# 2016_CARTE_MOFSET.net
KiCad netlist of a schematic drawn in Altium Designer
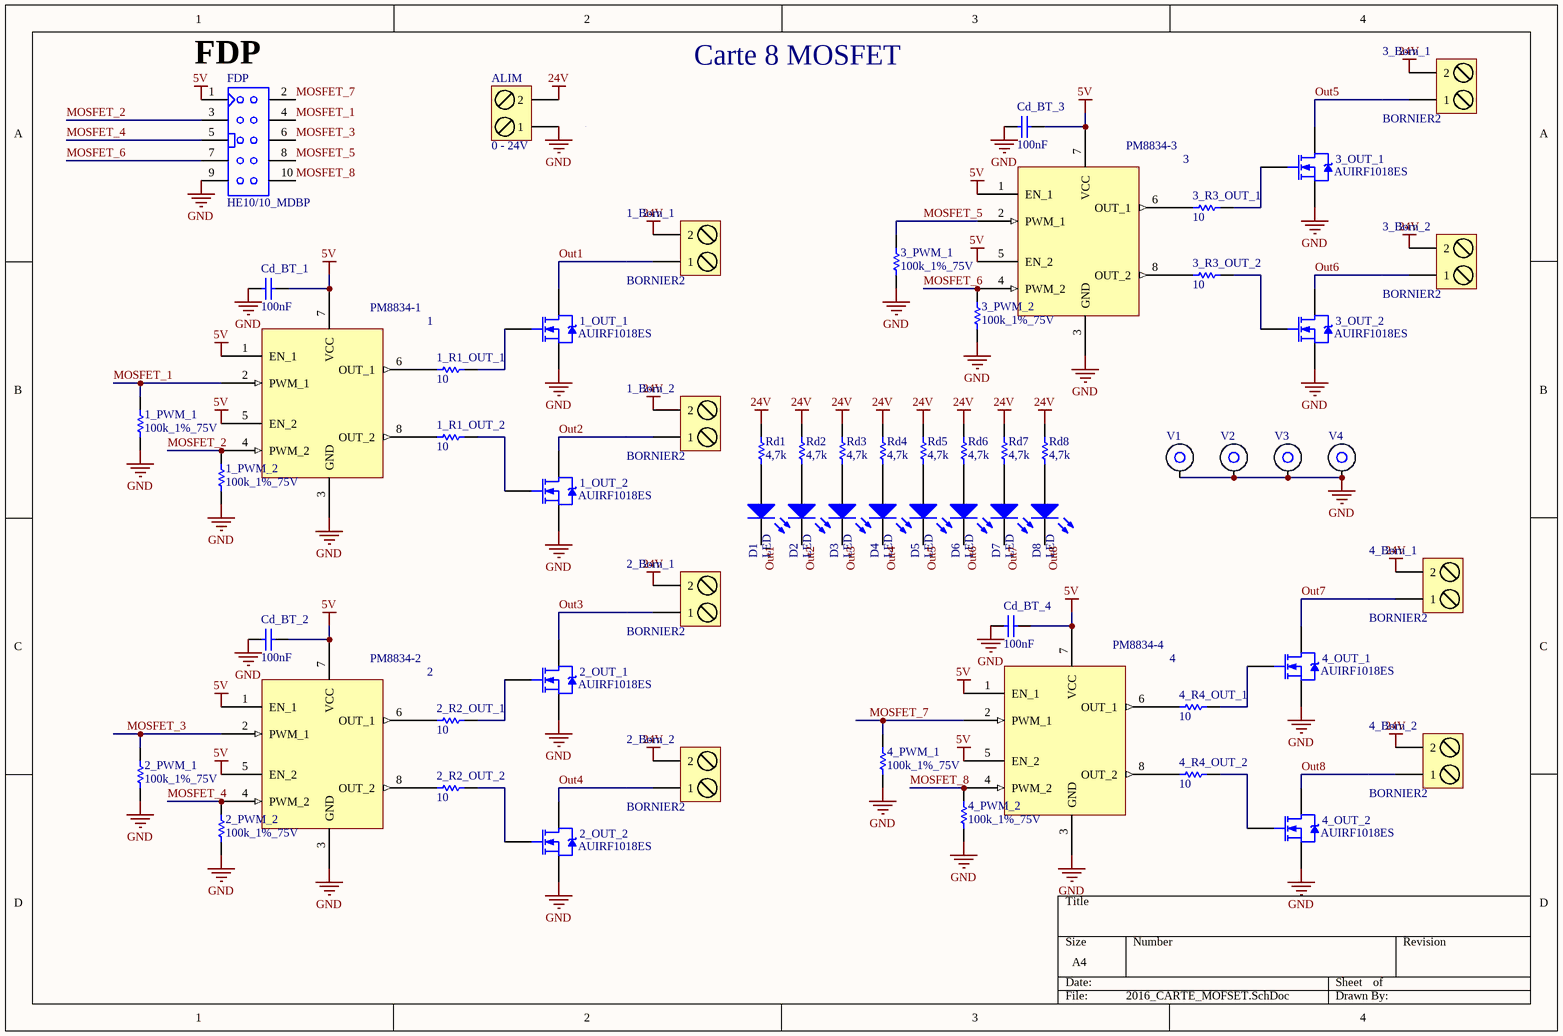
[diagram p0: 2016_CARTE_MOFSET.SchDoc]

(export (version "E")
  (design (tool "Eeschema 10.0.6"))
  (components
    (comp (ref "1")
      (value "PM8834-1")
      (footprint "SO8_N")
      (description "4 A dual low-side MOSFET driver")
      (libsource (lib "_ROBOT") (part "PM8834"))
    )
    (comp (ref "1_Born_1")
      (value "BORNIER2")
      (footprint "BORNIER2")
      (description "Terminal blocks, 2 pins, pitch=5mm")
      (libsource (lib "Connecteur") (part "BORNIER2"))
    )
    (comp (ref "1_Born_2")
      (value "BORNIER2")
      (footprint "BORNIER2")
      (description "Terminal blocks, 2 pins, pitch=5mm")
      (libsource (lib "Connecteur") (part "BORNIER2"))
    )
    (comp (ref "1_OUT_1")
      (value "AUIRF1018ES")
      (footprint "D2PAK_GROS_PAD")
      (description "HEXFET N-Channel Power MOSFET")
      (fields (field (name "PUBLISHER") "Altium Limited"))
      (libsource (lib "IR Discrete MOSFET - Power") (part "IRF1010S"))
    )
    (comp (ref "1_OUT_2")
      (value "AUIRF1018ES")
      (footprint "D2PAK_GROS_PAD")
      (description "HEXFET N-Channel Power MOSFET")
      (fields (field (name "PUBLISHER") "Altium Limited"))
      (libsource (lib "IR Discrete MOSFET - Power") (part "IRF1010S"))
    )
    (comp (ref "1_PWM_1")
      (value "100k_1%_75V")
      (footprint "R1206_N")
      (description "Resistor")
      (fields (field (name "PUBLISHER") "Altium Limited"))
      (libsource (lib "DG_Resistance") (part "Resistor"))
    )
    (comp (ref "1_PWM_2")
      (value "100k_1%_75V")
      (footprint "R1206_N")
      (description "Resistor")
      (fields (field (name "PUBLISHER") "Altium Limited"))
      (libsource (lib "DG_Resistance") (part "Resistor"))
    )
    (comp (ref "1_R1_OUT_1")
      (value "10")
      (footprint "R1206_N")
      (description "Resistor")
      (fields (field (name "PUBLISHER") "Altium Limited"))
      (libsource (lib "_ROBOT") (part "Resistor"))
    )
    (comp (ref "1_R1_OUT_2")
      (value "10")
      (footprint "R1206_N")
      (description "Resistor")
      (fields (field (name "PUBLISHER") "Altium Limited"))
      (libsource (lib "_ROBOT") (part "Resistor"))
    )
    (comp (ref "2")
      (value "PM8834-2")
      (footprint "SO8_N")
      (description "4 A dual low-side MOSFET driver")
      (libsource (lib "_ROBOT") (part "PM8834"))
    )
    (comp (ref "2_Born_1")
      (value "BORNIER2")
      (footprint "BORNIER2")
      (description "Terminal blocks, 2 pins, pitch=5mm")
      (libsource (lib "Connecteur") (part "BORNIER2"))
    )
    (comp (ref "2_Born_2")
      (value "BORNIER2")
      (footprint "BORNIER2")
      (description "Terminal blocks, 2 pins, pitch=5mm")
      (libsource (lib "Connecteur") (part "BORNIER2"))
    )
    (comp (ref "2_OUT_1")
      (value "AUIRF1018ES")
      (footprint "D2PAK_GROS_PAD")
      (description "HEXFET N-Channel Power MOSFET")
      (fields (field (name "PUBLISHER") "Altium Limited"))
      (libsource (lib "IR Discrete MOSFET - Power") (part "IRF1010S"))
    )
    (comp (ref "2_OUT_2")
      (value "AUIRF1018ES")
      (footprint "D2PAK_GROS_PAD")
      (description "HEXFET N-Channel Power MOSFET")
      (fields (field (name "PUBLISHER") "Altium Limited"))
      (libsource (lib "IR Discrete MOSFET - Power") (part "IRF1010S"))
    )
    (comp (ref "2_PWM_1")
      (value "100k_1%_75V")
      (footprint "R1206_N")
      (description "Resistor")
      (fields (field (name "PUBLISHER") "Altium Limited"))
      (libsource (lib "DG_Resistance") (part "Resistor"))
    )
    (comp (ref "2_PWM_2")
      (value "100k_1%_75V")
      (footprint "R1206_N")
      (description "Resistor")
      (fields (field (name "PUBLISHER") "Altium Limited"))
      (libsource (lib "DG_Resistance") (part "Resistor"))
    )
    (comp (ref "2_R2_OUT_1")
      (value "10")
      (footprint "R1206_N")
      (description "Resistor")
      (fields (field (name "PUBLISHER") "Altium Limited"))
      (libsource (lib "_ROBOT") (part "Resistor"))
    )
    (comp (ref "2_R2_OUT_2")
      (value "10")
      (footprint "R1206_N")
      (description "Resistor")
      (fields (field (name "PUBLISHER") "Altium Limited"))
      (libsource (lib "_ROBOT") (part "Resistor"))
    )
    (comp (ref "3")
      (value "PM8834-3")
      (footprint "SO8_N")
      (description "4 A dual low-side MOSFET driver")
      (libsource (lib "_ROBOT") (part "PM8834"))
    )
    (comp (ref "3_Born_1")
      (value "BORNIER2")
      (footprint "BORNIER2")
      (description "Terminal blocks, 2 pins, pitch=5mm")
      (libsource (lib "Connecteur") (part "BORNIER2"))
    )
    (comp (ref "3_Born_2")
      (value "BORNIER2")
      (footprint "BORNIER2")
      (description "Terminal blocks, 2 pins, pitch=5mm")
      (libsource (lib "Connecteur") (part "BORNIER2"))
    )
    (comp (ref "3_OUT_1")
      (value "AUIRF1018ES")
      (footprint "D2PAK_GROS_PAD")
      (description "HEXFET N-Channel Power MOSFET")
      (fields (field (name "PUBLISHER") "Altium Limited"))
      (libsource (lib "IR Discrete MOSFET - Power") (part "IRF1010S"))
    )
    (comp (ref "3_OUT_2")
      (value "AUIRF1018ES")
      (footprint "D2PAK_GROS_PAD")
      (description "HEXFET N-Channel Power MOSFET")
      (fields (field (name "PUBLISHER") "Altium Limited"))
      (libsource (lib "IR Discrete MOSFET - Power") (part "IRF1010S"))
    )
    (comp (ref "3_PWM_1")
      (value "100k_1%_75V")
      (footprint "R1206_N")
      (description "Resistor")
      (fields (field (name "PUBLISHER") "Altium Limited"))
      (libsource (lib "DG_Resistance") (part "Resistor"))
    )
    (comp (ref "3_PWM_2")
      (value "100k_1%_75V")
      (footprint "R1206_N")
      (description "Resistor")
      (fields (field (name "PUBLISHER") "Altium Limited"))
      (libsource (lib "DG_Resistance") (part "Resistor"))
    )
    (comp (ref "3_R3_OUT_1")
      (value "10")
      (footprint "R1206_N")
      (description "Resistor")
      (fields (field (name "PUBLISHER") "Altium Limited"))
      (libsource (lib "_ROBOT") (part "Resistor"))
    )
    (comp (ref "3_R3_OUT_2")
      (value "10")
      (footprint "R1206_N")
      (description "Resistor")
      (fields (field (name "PUBLISHER") "Altium Limited"))
      (libsource (lib "_ROBOT") (part "Resistor"))
    )
    (comp (ref "4")
      (value "PM8834-4")
      (footprint "SO8_N")
      (description "4 A dual low-side MOSFET driver")
      (libsource (lib "_ROBOT") (part "PM8834"))
    )
    (comp (ref "4_Born_1")
      (value "BORNIER2")
      (footprint "BORNIER2")
      (description "Terminal blocks, 2 pins, pitch=5mm")
      (libsource (lib "Connecteur") (part "BORNIER2"))
    )
    (comp (ref "4_Born_2")
      (value "BORNIER2")
      (footprint "BORNIER2")
      (description "Terminal blocks, 2 pins, pitch=5mm")
      (libsource (lib "Connecteur") (part "BORNIER2"))
    )
    (comp (ref "4_OUT_1")
      (value "AUIRF1018ES")
      (footprint "D2PAK_GROS_PAD")
      (description "HEXFET N-Channel Power MOSFET")
      (fields (field (name "PUBLISHER") "Altium Limited"))
      (libsource (lib "IR Discrete MOSFET - Power") (part "IRF1010S"))
    )
    (comp (ref "4_OUT_2")
      (value "AUIRF1018ES")
      (footprint "D2PAK_GROS_PAD")
      (description "HEXFET N-Channel Power MOSFET")
      (fields (field (name "PUBLISHER") "Altium Limited"))
      (libsource (lib "IR Discrete MOSFET - Power") (part "IRF1010S"))
    )
    (comp (ref "4_PWM_1")
      (value "100k_1%_75V")
      (footprint "R1206_N")
      (description "Resistor")
      (fields (field (name "PUBLISHER") "Altium Limited"))
      (libsource (lib "DG_Resistance") (part "Resistor"))
    )
    (comp (ref "4_PWM_2")
      (value "100k_1%_75V")
      (footprint "R1206_N")
      (description "Resistor")
      (fields (field (name "PUBLISHER") "Altium Limited"))
      (libsource (lib "DG_Resistance") (part "Resistor"))
    )
    (comp (ref "4_R4_OUT_1")
      (value "10")
      (footprint "R1206_N")
      (description "Resistor")
      (fields (field (name "PUBLISHER") "Altium Limited"))
      (libsource (lib "_ROBOT") (part "Resistor"))
    )
    (comp (ref "4_R4_OUT_2")
      (value "10")
      (footprint "R1206_N")
      (description "Resistor")
      (fields (field (name "PUBLISHER") "Altium Limited"))
      (libsource (lib "_ROBOT") (part "Resistor"))
    )
    (comp (ref "ALIM")
      (value "0 - 24V")
      (footprint "BORNIER2_FEM_COUDE")
      (description "Terminal blocks, 2 pins, pitch=5mm")
      (libsource (lib "miniprojet") (part "BORNIER2"))
    )
    (comp (ref "Cd_BT_1")
      (value "100nF")
      (footprint "C0805_N")
      (description "Capacitor")
      (fields (field (name "PUBLISHER") "Altium Limited"))
      (libsource (lib "_ROBOT") (part "Condensateur"))
    )
    (comp (ref "Cd_BT_2")
      (value "100nF")
      (footprint "C0805_N")
      (description "Capacitor")
      (fields (field (name "PUBLISHER") "Altium Limited"))
      (libsource (lib "_ROBOT") (part "Condensateur"))
    )
    (comp (ref "Cd_BT_3")
      (value "100nF")
      (footprint "C0805_N")
      (description "Capacitor")
      (fields (field (name "PUBLISHER") "Altium Limited"))
      (libsource (lib "_ROBOT") (part "Condensateur"))
    )
    (comp (ref "Cd_BT_4")
      (value "100nF")
      (footprint "C0805_N")
      (description "Capacitor")
      (fields (field (name "PUBLISHER") "Altium Limited"))
      (libsource (lib "_ROBOT") (part "Condensateur"))
    )
    (comp (ref "D1")
      (value "LED")
      (footprint "LED_0805")
      (description "Typical LED")
      (fields (field (name "PUBLISHER") "Altium Limited"))
      (libsource (lib "_ROBOT") (part "LED"))
    )
    (comp (ref "D2")
      (value "LED")
      (footprint "LED_0805")
      (description "Typical LED")
      (fields (field (name "PUBLISHER") "Altium Limited"))
      (libsource (lib "_ROBOT") (part "LED"))
    )
    (comp (ref "D3")
      (value "LED")
      (footprint "LED_0805")
      (description "Typical LED")
      (fields (field (name "PUBLISHER") "Altium Limited"))
      (libsource (lib "_ROBOT") (part "LED"))
    )
    (comp (ref "D4")
      (value "LED")
      (footprint "LED_0805")
      (description "Typical LED")
      (fields (field (name "PUBLISHER") "Altium Limited"))
      (libsource (lib "_ROBOT") (part "LED"))
    )
    (comp (ref "D5")
      (value "LED")
      (footprint "LED_0805")
      (description "Typical LED")
      (fields (field (name "PUBLISHER") "Altium Limited"))
      (libsource (lib "_ROBOT") (part "LED"))
    )
    (comp (ref "D6")
      (value "LED")
      (footprint "LED_0805")
      (description "Typical LED")
      (fields (field (name "PUBLISHER") "Altium Limited"))
      (libsource (lib "_ROBOT") (part "LED"))
    )
    (comp (ref "D7")
      (value "LED")
      (footprint "LED_0805")
      (description "Typical LED")
      (fields (field (name "PUBLISHER") "Altium Limited"))
      (libsource (lib "_ROBOT") (part "LED"))
    )
    (comp (ref "D8")
      (value "LED")
      (footprint "LED_0805")
      (description "Typical LED")
      (fields (field (name "PUBLISHER") "Altium Limited"))
      (libsource (lib "_ROBOT") (part "LED"))
    )
    (comp (ref "FDP")
      (value "HE10/10_MALE_DROIT_BAS_PROFIL")
      (footprint "HE10/10_M_D_BP")
      (description "EMBASE HE10/10 MALE DROIT BAS PROFIL")
      (fields (field (name "TYPE") "HE10/10_MDBP"))
      (libsource (lib "connecteurs") (part "HE10/10_MALE_DROIT_BAS_PROFIL"))
    )
    (comp (ref "Rd1")
      (value "4,7k")
      (footprint "R1206_N")
      (description "Resistor")
      (fields (field (name "PUBLISHER") "Altium Limited"))
      (libsource (lib "_ROBOT") (part "Resistor"))
    )
    (comp (ref "Rd2")
      (value "4,7k")
      (footprint "R1206_N")
      (description "Resistor")
      (fields (field (name "PUBLISHER") "Altium Limited"))
      (libsource (lib "_ROBOT") (part "Resistor"))
    )
    (comp (ref "Rd3")
      (value "4,7k")
      (footprint "R1206_N")
      (description "Resistor")
      (fields (field (name "PUBLISHER") "Altium Limited"))
      (libsource (lib "_ROBOT") (part "Resistor"))
    )
    (comp (ref "Rd4")
      (value "4,7k")
      (footprint "R1206_N")
      (description "Resistor")
      (fields (field (name "PUBLISHER") "Altium Limited"))
      (libsource (lib "_ROBOT") (part "Resistor"))
    )
    (comp (ref "Rd5")
      (value "4,7k")
      (footprint "R1206_N")
      (description "Resistor")
      (fields (field (name "PUBLISHER") "Altium Limited"))
      (libsource (lib "_ROBOT") (part "Resistor"))
    )
    (comp (ref "Rd6")
      (value "4,7k")
      (footprint "R1206_N")
      (description "Resistor")
      (fields (field (name "PUBLISHER") "Altium Limited"))
      (libsource (lib "_ROBOT") (part "Resistor"))
    )
    (comp (ref "Rd7")
      (value "4,7k")
      (footprint "R1206_N")
      (description "Resistor")
      (fields (field (name "PUBLISHER") "Altium Limited"))
      (libsource (lib "_ROBOT") (part "Resistor"))
    )
    (comp (ref "Rd8")
      (value "4,7k")
      (footprint "R1206_N")
      (description "Resistor")
      (fields (field (name "PUBLISHER") "Altium Limited"))
      (libsource (lib "_ROBOT") (part "Resistor"))
    )
    (comp (ref "V1")
      (value "Entretoise WURTH CMS")
      (footprint "ENTRETOISE_CMS")
      (description "Entretoise Wurth")
      (fields (field (name "PUBLISHER") "Damien Guitton"))
      (libsource (lib "_ROBOT") (part "Entretoise WURTH CMS"))
    )
    (comp (ref "V2")
      (value "Entretoise WURTH CMS")
      (footprint "ENTRETOISE_CMS")
      (description "Entretoise Wurth")
      (fields (field (name "PUBLISHER") "Damien Guitton"))
      (libsource (lib "_ROBOT") (part "Entretoise WURTH CMS"))
    )
    (comp (ref "V3")
      (value "Entretoise WURTH CMS")
      (footprint "ENTRETOISE_CMS")
      (description "Entretoise Wurth")
      (fields (field (name "PUBLISHER") "Damien Guitton"))
      (libsource (lib "_ROBOT") (part "Entretoise WURTH CMS"))
    )
    (comp (ref "V4")
      (value "Entretoise WURTH CMS")
      (footprint "ENTRETOISE_CMS")
      (description "Entretoise Wurth")
      (fields (field (name "PUBLISHER") "Damien Guitton"))
      (libsource (lib "_ROBOT") (part "Entretoise WURTH CMS"))
    )
  )
  (nets
    (net (code "1") (name "/MOSFET_1") (class "Default")
      (node (ref "1") (pin "2") (pinfunction "PWM_1_2") (pintype "input"))
      (node (ref "1_PWM_1") (pin "2") (pinfunction "2_2") (pintype "passive"))
      (node (ref "FDP") (pin "4") (pinfunction "4_4") (pintype "passive"))
    )
    (net (code "2") (name "/MOSFET_2") (class "Default")
      (node (ref "1") (pin "4") (pinfunction "PWM_2_4") (pintype "input"))
      (node (ref "1_PWM_2") (pin "2") (pinfunction "2_2") (pintype "passive"))
      (node (ref "FDP") (pin "3") (pinfunction "3_3") (pintype "passive"))
    )
    (net (code "3") (name "/MOSFET_3") (class "Default")
      (node (ref "2") (pin "2") (pinfunction "PWM_1_2") (pintype "input"))
      (node (ref "2_PWM_1") (pin "2") (pinfunction "2_2") (pintype "passive"))
      (node (ref "FDP") (pin "6") (pinfunction "6_6") (pintype "passive"))
    )
    (net (code "4") (name "/MOSFET_4") (class "Default")
      (node (ref "2") (pin "4") (pinfunction "PWM_2_4") (pintype "input"))
      (node (ref "2_PWM_2") (pin "2") (pinfunction "2_2") (pintype "passive"))
      (node (ref "FDP") (pin "5") (pinfunction "5_5") (pintype "passive"))
    )
    (net (code "5") (name "/MOSFET_5") (class "Default")
      (node (ref "3") (pin "2") (pinfunction "PWM_1_2") (pintype "input"))
      (node (ref "3_PWM_1") (pin "2") (pinfunction "2_2") (pintype "passive"))
      (node (ref "FDP") (pin "8") (pinfunction "8_8") (pintype "passive"))
    )
    (net (code "6") (name "/MOSFET_6") (class "Default")
      (node (ref "3") (pin "4") (pinfunction "PWM_2_4") (pintype "input"))
      (node (ref "3_PWM_2") (pin "2") (pinfunction "2_2") (pintype "passive"))
      (node (ref "FDP") (pin "7") (pinfunction "7_7") (pintype "passive"))
    )
    (net (code "7") (name "/MOSFET_7") (class "Default")
      (node (ref "4") (pin "2") (pinfunction "PWM_1_2") (pintype "input"))
      (node (ref "4_PWM_1") (pin "2") (pinfunction "2_2") (pintype "passive"))
      (node (ref "FDP") (pin "2") (pinfunction "2_2") (pintype "passive"))
    )
    (net (code "8") (name "/MOSFET_8") (class "Default")
      (node (ref "4") (pin "4") (pinfunction "PWM_2_4") (pintype "input"))
      (node (ref "4_PWM_2") (pin "2") (pinfunction "2_2") (pintype "passive"))
      (node (ref "FDP") (pin "10") (pinfunction "10_10") (pintype "passive"))
    )
    (net (code "9") (name "/Out1") (class "Default")
      (node (ref "1_Born_1") (pin "1") (pinfunction "1_1") (pintype "passive"))
      (node (ref "1_OUT_1") (pin "2") (pinfunction "D_2") (pintype "passive"))
      (node (ref "D1") (pin "2") (pinfunction "K_2") (pintype "passive"))
    )
    (net (code "10") (name "/Out2") (class "Default")
      (node (ref "1_Born_2") (pin "1") (pinfunction "1_1") (pintype "passive"))
      (node (ref "1_OUT_2") (pin "2") (pinfunction "D_2") (pintype "passive"))
      (node (ref "D2") (pin "2") (pinfunction "K_2") (pintype "passive"))
    )
    (net (code "11") (name "/Out3") (class "Default")
      (node (ref "2_Born_1") (pin "1") (pinfunction "1_1") (pintype "passive"))
      (node (ref "2_OUT_1") (pin "2") (pinfunction "D_2") (pintype "passive"))
      (node (ref "D3") (pin "2") (pinfunction "K_2") (pintype "passive"))
    )
    (net (code "12") (name "/Out4") (class "Default")
      (node (ref "2_Born_2") (pin "1") (pinfunction "1_1") (pintype "passive"))
      (node (ref "2_OUT_2") (pin "2") (pinfunction "D_2") (pintype "passive"))
      (node (ref "D4") (pin "2") (pinfunction "K_2") (pintype "passive"))
    )
    (net (code "13") (name "/Out5") (class "Default")
      (node (ref "3_Born_1") (pin "1") (pinfunction "1_1") (pintype "passive"))
      (node (ref "3_OUT_1") (pin "2") (pinfunction "D_2") (pintype "passive"))
      (node (ref "D5") (pin "2") (pinfunction "K_2") (pintype "passive"))
    )
    (net (code "14") (name "/Out6") (class "Default")
      (node (ref "3_Born_2") (pin "1") (pinfunction "1_1") (pintype "passive"))
      (node (ref "3_OUT_2") (pin "2") (pinfunction "D_2") (pintype "passive"))
      (node (ref "D6") (pin "2") (pinfunction "K_2") (pintype "passive"))
    )
    (net (code "15") (name "/Out7") (class "Default")
      (node (ref "4_Born_1") (pin "1") (pinfunction "1_1") (pintype "passive"))
      (node (ref "4_OUT_1") (pin "2") (pinfunction "D_2") (pintype "passive"))
      (node (ref "D7") (pin "2") (pinfunction "K_2") (pintype "passive"))
    )
    (net (code "16") (name "/Out8") (class "Default")
      (node (ref "4_Born_2") (pin "1") (pinfunction "1_1") (pintype "passive"))
      (node (ref "4_OUT_2") (pin "2") (pinfunction "D_2") (pintype "passive"))
      (node (ref "D8") (pin "2") (pinfunction "K_2") (pintype "passive"))
    )
    (net (code "17") (name "5V") (class "Default")
      (node (ref "1") (pin "1") (pinfunction "EN_1_1") (pintype "passive"))
      (node (ref "1") (pin "5") (pinfunction "EN_2_5") (pintype "passive"))
      (node (ref "1") (pin "7") (pinfunction "VCC_7") (pintype "power_in"))
      (node (ref "2") (pin "1") (pinfunction "EN_1_1") (pintype "passive"))
      (node (ref "2") (pin "5") (pinfunction "EN_2_5") (pintype "passive"))
      (node (ref "2") (pin "7") (pinfunction "VCC_7") (pintype "power_in"))
      (node (ref "3") (pin "1") (pinfunction "EN_1_1") (pintype "passive"))
      (node (ref "3") (pin "5") (pinfunction "EN_2_5") (pintype "passive"))
      (node (ref "3") (pin "7") (pinfunction "VCC_7") (pintype "power_in"))
      (node (ref "4") (pin "1") (pinfunction "EN_1_1") (pintype "passive"))
      (node (ref "4") (pin "5") (pinfunction "EN_2_5") (pintype "passive"))
      (node (ref "4") (pin "7") (pinfunction "VCC_7") (pintype "power_in"))
      (node (ref "Cd_BT_1") (pin "2") (pinfunction "2_2") (pintype "passive"))
      (node (ref "Cd_BT_2") (pin "2") (pinfunction "2_2") (pintype "passive"))
      (node (ref "Cd_BT_3") (pin "2") (pinfunction "2_2") (pintype "passive"))
      (node (ref "Cd_BT_4") (pin "2") (pinfunction "2_2") (pintype "passive"))
      (node (ref "FDP") (pin "1") (pinfunction "1_1") (pintype "passive"))
    )
    (net (code "18") (name "24V") (class "Default")
      (node (ref "1_Born_1") (pin "2") (pinfunction "2_2") (pintype "passive"))
      (node (ref "1_Born_2") (pin "2") (pinfunction "2_2") (pintype "passive"))
      (node (ref "2_Born_1") (pin "2") (pinfunction "2_2") (pintype "passive"))
      (node (ref "2_Born_2") (pin "2") (pinfunction "2_2") (pintype "passive"))
      (node (ref "3_Born_1") (pin "2") (pinfunction "2_2") (pintype "passive"))
      (node (ref "3_Born_2") (pin "2") (pinfunction "2_2") (pintype "passive"))
      (node (ref "4_Born_1") (pin "2") (pinfunction "2_2") (pintype "passive"))
      (node (ref "4_Born_2") (pin "2") (pinfunction "2_2") (pintype "passive"))
      (node (ref "ALIM") (pin "2") (pinfunction "2_2") (pintype "passive"))
      (node (ref "Rd1") (pin "1") (pinfunction "1_1") (pintype "passive"))
      (node (ref "Rd2") (pin "1") (pinfunction "1_1") (pintype "passive"))
      (node (ref "Rd3") (pin "1") (pinfunction "1_1") (pintype "passive"))
      (node (ref "Rd4") (pin "1") (pinfunction "1_1") (pintype "passive"))
      (node (ref "Rd5") (pin "1") (pinfunction "1_1") (pintype "passive"))
      (node (ref "Rd6") (pin "1") (pinfunction "1_1") (pintype "passive"))
      (node (ref "Rd7") (pin "1") (pinfunction "1_1") (pintype "passive"))
      (node (ref "Rd8") (pin "1") (pinfunction "1_1") (pintype "passive"))
    )
    (net (code "19") (name "GND") (class "Default")
      (node (ref "1") (pin "3") (pinfunction "GND_3") (pintype "power_in"))
      (node (ref "1_OUT_1") (pin "3") (pinfunction "S_3") (pintype "passive"))
      (node (ref "1_OUT_2") (pin "3") (pinfunction "S_3") (pintype "passive"))
      (node (ref "1_PWM_1") (pin "1") (pinfunction "1_1") (pintype "passive"))
      (node (ref "1_PWM_2") (pin "1") (pinfunction "1_1") (pintype "passive"))
      (node (ref "2") (pin "3") (pinfunction "GND_3") (pintype "power_in"))
      (node (ref "2_OUT_1") (pin "3") (pinfunction "S_3") (pintype "passive"))
      (node (ref "2_OUT_2") (pin "3") (pinfunction "S_3") (pintype "passive"))
      (node (ref "2_PWM_1") (pin "1") (pinfunction "1_1") (pintype "passive"))
      (node (ref "2_PWM_2") (pin "1") (pinfunction "1_1") (pintype "passive"))
      (node (ref "3") (pin "3") (pinfunction "GND_3") (pintype "power_in"))
      (node (ref "3_OUT_1") (pin "3") (pinfunction "S_3") (pintype "passive"))
      (node (ref "3_OUT_2") (pin "3") (pinfunction "S_3") (pintype "passive"))
      (node (ref "3_PWM_1") (pin "1") (pinfunction "1_1") (pintype "passive"))
      (node (ref "3_PWM_2") (pin "1") (pinfunction "1_1") (pintype "passive"))
      (node (ref "4") (pin "3") (pinfunction "GND_3") (pintype "power_in"))
      (node (ref "4_OUT_1") (pin "3") (pinfunction "S_3") (pintype "passive"))
      (node (ref "4_OUT_2") (pin "3") (pinfunction "S_3") (pintype "passive"))
      (node (ref "4_PWM_1") (pin "1") (pinfunction "1_1") (pintype "passive"))
      (node (ref "4_PWM_2") (pin "1") (pinfunction "1_1") (pintype "passive"))
      (node (ref "ALIM") (pin "1") (pinfunction "1_1") (pintype "passive"))
      (node (ref "Cd_BT_1") (pin "1") (pinfunction "1_1") (pintype "passive"))
      (node (ref "Cd_BT_2") (pin "1") (pinfunction "1_1") (pintype "passive"))
      (node (ref "Cd_BT_3") (pin "1") (pinfunction "1_1") (pintype "passive"))
      (node (ref "Cd_BT_4") (pin "1") (pinfunction "1_1") (pintype "passive"))
      (node (ref "FDP") (pin "9") (pinfunction "9_9") (pintype "passive"))
      (node (ref "V1") (pin "1") (pinfunction "1_1") (pintype "passive"))
      (node (ref "V2") (pin "1") (pinfunction "1_1") (pintype "passive"))
      (node (ref "V3") (pin "1") (pinfunction "1_1") (pintype "passive"))
      (node (ref "V4") (pin "1") (pinfunction "1_1") (pintype "passive"))
    )
    (net (code "20") (name "Net-(1-OUT_1)") (class "Default")
      (node (ref "1") (pin "6") (pinfunction "OUT_1_6") (pintype "output"))
      (node (ref "1_R1_OUT_1") (pin "1") (pinfunction "1_1") (pintype "passive"))
    )
    (net (code "21") (name "Net-(1-OUT_2)") (class "Default")
      (node (ref "1") (pin "8") (pinfunction "OUT_2_8") (pintype "output"))
      (node (ref "1_R1_OUT_2") (pin "1") (pinfunction "1_1") (pintype "passive"))
    )
    (net (code "22") (name "Net-(1_OUT_1-G)") (class "Default")
      (node (ref "1_OUT_1") (pin "1") (pinfunction "G_1") (pintype "passive"))
      (node (ref "1_R1_OUT_1") (pin "2") (pinfunction "2_2") (pintype "passive"))
    )
    (net (code "23") (name "Net-(1_OUT_2-G)") (class "Default")
      (node (ref "1_OUT_2") (pin "1") (pinfunction "G_1") (pintype "passive"))
      (node (ref "1_R1_OUT_2") (pin "2") (pinfunction "2_2") (pintype "passive"))
    )
    (net (code "24") (name "Net-(2-OUT_1)") (class "Default")
      (node (ref "2") (pin "6") (pinfunction "OUT_1_6") (pintype "output"))
      (node (ref "2_R2_OUT_1") (pin "1") (pinfunction "1_1") (pintype "passive"))
    )
    (net (code "25") (name "Net-(2-OUT_2)") (class "Default")
      (node (ref "2") (pin "8") (pinfunction "OUT_2_8") (pintype "output"))
      (node (ref "2_R2_OUT_2") (pin "1") (pinfunction "1_1") (pintype "passive"))
    )
    (net (code "26") (name "Net-(2_OUT_1-G)") (class "Default")
      (node (ref "2_OUT_1") (pin "1") (pinfunction "G_1") (pintype "passive"))
      (node (ref "2_R2_OUT_1") (pin "2") (pinfunction "2_2") (pintype "passive"))
    )
    (net (code "27") (name "Net-(2_OUT_2-G)") (class "Default")
      (node (ref "2_OUT_2") (pin "1") (pinfunction "G_1") (pintype "passive"))
      (node (ref "2_R2_OUT_2") (pin "2") (pinfunction "2_2") (pintype "passive"))
    )
    (net (code "28") (name "Net-(3-OUT_1)") (class "Default")
      (node (ref "3") (pin "6") (pinfunction "OUT_1_6") (pintype "output"))
      (node (ref "3_R3_OUT_1") (pin "1") (pinfunction "1_1") (pintype "passive"))
    )
    (net (code "29") (name "Net-(3-OUT_2)") (class "Default")
      (node (ref "3") (pin "8") (pinfunction "OUT_2_8") (pintype "output"))
      (node (ref "3_R3_OUT_2") (pin "1") (pinfunction "1_1") (pintype "passive"))
    )
    (net (code "30") (name "Net-(3_OUT_1-G)") (class "Default")
      (node (ref "3_OUT_1") (pin "1") (pinfunction "G_1") (pintype "passive"))
      (node (ref "3_R3_OUT_1") (pin "2") (pinfunction "2_2") (pintype "passive"))
    )
    (net (code "31") (name "Net-(3_OUT_2-G)") (class "Default")
      (node (ref "3_OUT_2") (pin "1") (pinfunction "G_1") (pintype "passive"))
      (node (ref "3_R3_OUT_2") (pin "2") (pinfunction "2_2") (pintype "passive"))
    )
    (net (code "32") (name "Net-(4-OUT_1)") (class "Default")
      (node (ref "4") (pin "6") (pinfunction "OUT_1_6") (pintype "output"))
      (node (ref "4_R4_OUT_1") (pin "1") (pinfunction "1_1") (pintype "passive"))
    )
    (net (code "33") (name "Net-(4-OUT_2)") (class "Default")
      (node (ref "4") (pin "8") (pinfunction "OUT_2_8") (pintype "output"))
      (node (ref "4_R4_OUT_2") (pin "1") (pinfunction "1_1") (pintype "passive"))
    )
    (net (code "34") (name "Net-(4_OUT_1-G)") (class "Default")
      (node (ref "4_OUT_1") (pin "1") (pinfunction "G_1") (pintype "passive"))
      (node (ref "4_R4_OUT_1") (pin "2") (pinfunction "2_2") (pintype "passive"))
    )
    (net (code "35") (name "Net-(4_OUT_2-G)") (class "Default")
      (node (ref "4_OUT_2") (pin "1") (pinfunction "G_1") (pintype "passive"))
      (node (ref "4_R4_OUT_2") (pin "2") (pinfunction "2_2") (pintype "passive"))
    )
    (net (code "36") (name "Net-(D1-A)") (class "Default")
      (node (ref "D1") (pin "1") (pinfunction "A_1") (pintype "passive"))
      (node (ref "Rd1") (pin "2") (pinfunction "2_2") (pintype "passive"))
    )
    (net (code "37") (name "Net-(D2-A)") (class "Default")
      (node (ref "D2") (pin "1") (pinfunction "A_1") (pintype "passive"))
      (node (ref "Rd2") (pin "2") (pinfunction "2_2") (pintype "passive"))
    )
    (net (code "38") (name "Net-(D3-A)") (class "Default")
      (node (ref "D3") (pin "1") (pinfunction "A_1") (pintype "passive"))
      (node (ref "Rd3") (pin "2") (pinfunction "2_2") (pintype "passive"))
    )
    (net (code "39") (name "Net-(D4-A)") (class "Default")
      (node (ref "D4") (pin "1") (pinfunction "A_1") (pintype "passive"))
      (node (ref "Rd4") (pin "2") (pinfunction "2_2") (pintype "passive"))
    )
    (net (code "40") (name "Net-(D5-A)") (class "Default")
      (node (ref "D5") (pin "1") (pinfunction "A_1") (pintype "passive"))
      (node (ref "Rd5") (pin "2") (pinfunction "2_2") (pintype "passive"))
    )
    (net (code "41") (name "Net-(D6-A)") (class "Default")
      (node (ref "D6") (pin "1") (pinfunction "A_1") (pintype "passive"))
      (node (ref "Rd6") (pin "2") (pinfunction "2_2") (pintype "passive"))
    )
    (net (code "42") (name "Net-(D7-A)") (class "Default")
      (node (ref "D7") (pin "1") (pinfunction "A_1") (pintype "passive"))
      (node (ref "Rd7") (pin "2") (pinfunction "2_2") (pintype "passive"))
    )
    (net (code "43") (name "Net-(D8-A)") (class "Default")
      (node (ref "D8") (pin "1") (pinfunction "A_1") (pintype "passive"))
      (node (ref "Rd8") (pin "2") (pinfunction "2_2") (pintype "passive"))
    )
  )
)
